# DAPLink.net
KiCad netlist of a schematic drawn in Altium Designer
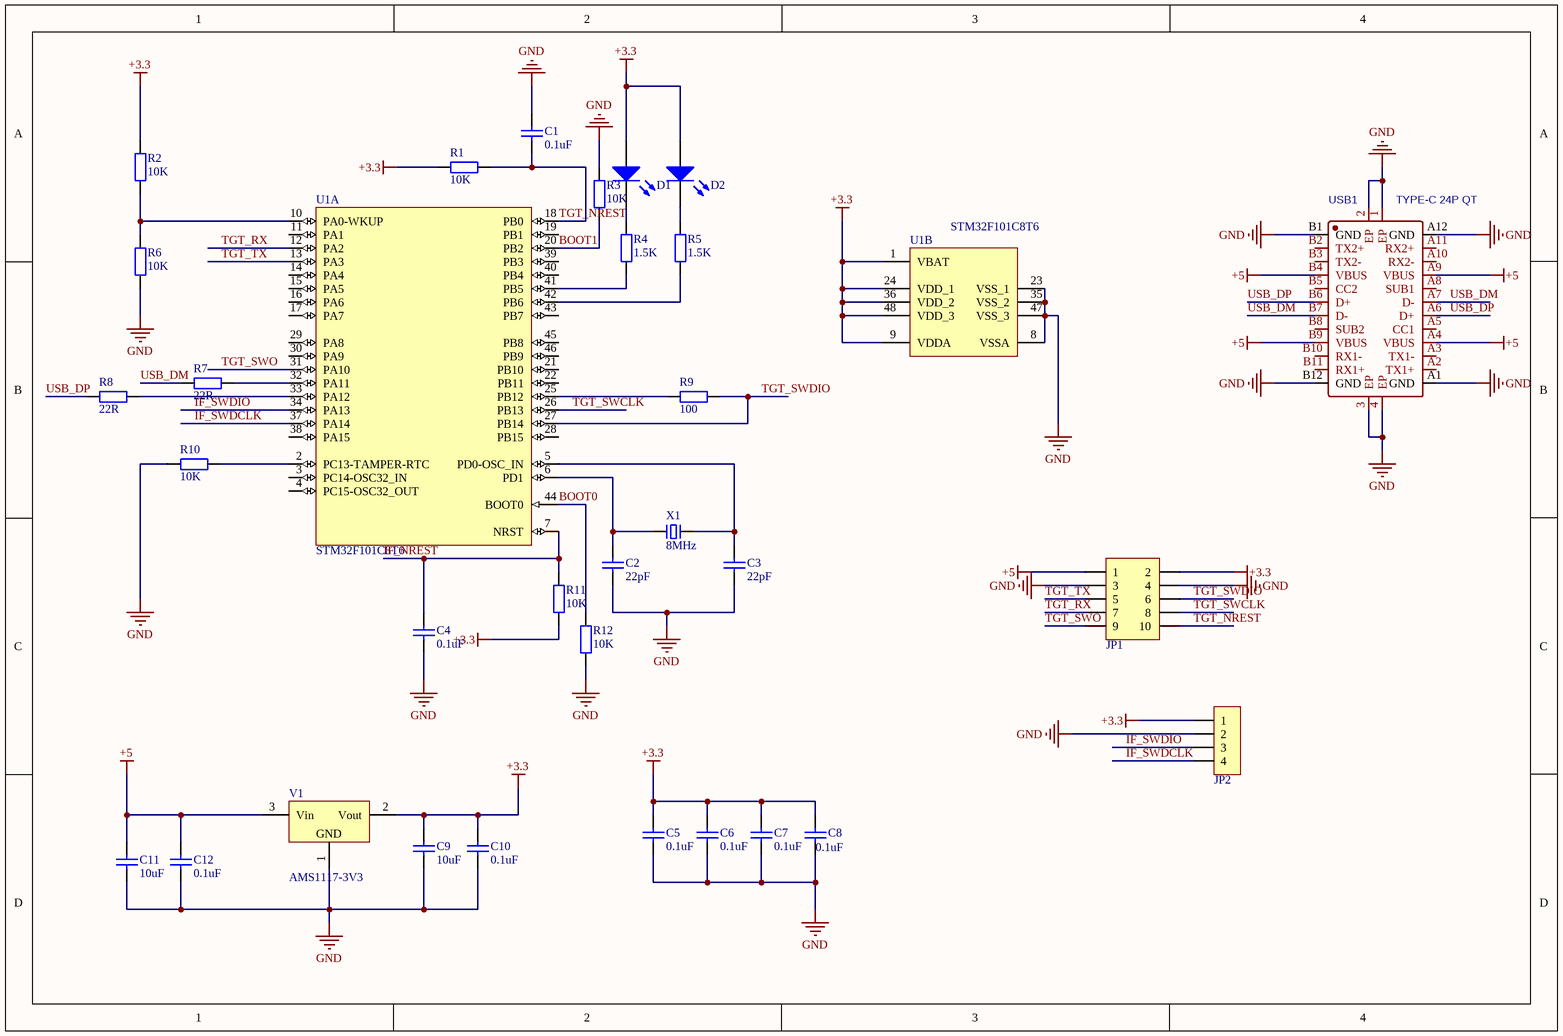
[diagram p0: DAPLink.SchDoc]

(export (version "E")
  (design (tool "Eeschema 10.0.6"))
  (components
    (comp (ref "C1")
      (value "0.1uF")
      (footprint "C0603_L")
      (description "贴片电容")
      (libsource (lib "DAPLink") (part "C"))
    )
    (comp (ref "C2")
      (value "22pF")
      (footprint "C0603_L")
      (description "贴片电容")
      (libsource (lib "DAPLink") (part "C"))
    )
    (comp (ref "C3")
      (value "22pF")
      (footprint "C0603_L")
      (description "贴片电容")
      (libsource (lib "DAPLink") (part "C"))
    )
    (comp (ref "C4")
      (value "0.1uF")
      (footprint "C0603_L")
      (description "贴片电容")
      (libsource (lib "DAPLink") (part "C"))
    )
    (comp (ref "C5")
      (value "0.1uF")
      (footprint "C0603_L")
      (description "贴片电容")
      (libsource (lib "DAPLink") (part "C"))
    )
    (comp (ref "C6")
      (value "0.1uF")
      (footprint "C0603_L")
      (description "贴片电容")
      (libsource (lib "DAPLink") (part "C"))
    )
    (comp (ref "C7")
      (value "0.1uF")
      (footprint "C0603_L")
      (description "贴片电容")
      (libsource (lib "DAPLink") (part "C"))
    )
    (comp (ref "C8")
      (value "0.1uF")
      (footprint "C0603_L")
      (description "贴片电容")
      (libsource (lib "DAPLink") (part "C"))
    )
    (comp (ref "C9")
      (value "10uF")
      (footprint "C0603_L")
      (description "贴片电容")
      (libsource (lib "DAPLink") (part "C"))
    )
    (comp (ref "C10")
      (value "0.1uF")
      (footprint "C0603_L")
      (description "贴片电容")
      (libsource (lib "DAPLink") (part "C"))
    )
    (comp (ref "C11")
      (value "10uF")
      (footprint "C0603_L")
      (description "贴片电容")
      (libsource (lib "DAPLink") (part "C"))
    )
    (comp (ref "C12")
      (value "0.1uF")
      (footprint "C0603_L")
      (description "贴片电容")
      (libsource (lib "DAPLink") (part "C"))
    )
    (comp (ref "D1")
      (value "LED")
      (footprint "LED0603_B")
      (description "发光二极管")
      (libsource (lib "DAPLink") (part "LED"))
    )
    (comp (ref "D2")
      (value "LED")
      (footprint "LED0603_G")
      (description "发光二极管")
      (libsource (lib "DAPLink") (part "LED"))
    )
    (comp (ref "JP1")
      (value "Header 5X2")
      (footprint "HDR2.54-WI-2x5P")
      (description "5*2P接插件")
      (libsource (lib "5.4 - 接插件-脚距2.54 (100mil) ") (part "Header 5X2"))
    )
    (comp (ref "JP2")
      (value "HDR-1X4")
      (footprint "HDR1.27-LI-4P")
      (description "4P接插件")
      (libsource (lib "5.1 - 接插件-脚距1.27") (part "Header 4"))
    )
    (comp (ref "R1")
      (value "10K")
      (footprint "R0603_L")
      (description "贴片电阻")
      (libsource (lib "DAPLink") (part "R"))
    )
    (comp (ref "R2")
      (value "10K")
      (footprint "R0603_L")
      (description "贴片电阻")
      (libsource (lib "DAPLink") (part "R"))
    )
    (comp (ref "R3")
      (value "10K")
      (footprint "R0603_L")
      (description "贴片电阻")
      (libsource (lib "DAPLink") (part "R"))
    )
    (comp (ref "R4")
      (value "1.5K")
      (footprint "R0603_L")
      (description "贴片电阻")
      (libsource (lib "DAPLink") (part "R"))
    )
    (comp (ref "R5")
      (value "1.5K")
      (footprint "R0603_L")
      (description "贴片电阻")
      (libsource (lib "DAPLink") (part "R"))
    )
    (comp (ref "R6")
      (value "10K")
      (footprint "R0603_L")
      (description "贴片电阻")
      (libsource (lib "DAPLink") (part "R"))
    )
    (comp (ref "R7")
      (value "22R")
      (footprint "R0603_L")
      (description "贴片电阻")
      (libsource (lib "DAPLink") (part "R"))
    )
    (comp (ref "R8")
      (value "22R")
      (footprint "R0603_L")
      (description "贴片电阻")
      (libsource (lib "DAPLink") (part "R"))
    )
    (comp (ref "R9")
      (value "100")
      (footprint "R0603_L")
      (description "贴片电阻")
      (libsource (lib "DAPLink") (part "R"))
    )
    (comp (ref "R10")
      (value "10K")
      (footprint "R0603_L")
      (description "贴片电阻")
      (libsource (lib "DAPLink") (part "R"))
    )
    (comp (ref "R11")
      (value "10K")
      (footprint "R0603_L")
      (description "贴片电阻")
      (libsource (lib "DAPLink") (part "R"))
    )
    (comp (ref "R12")
      (value "10K")
      (footprint "R0603_L")
      (description "贴片电阻")
      (libsource (lib "DAPLink") (part "R"))
    )
    (comp (ref "U1")
      (value "STM32F101C8T6")
      (footprint "LQFP48_N")
      (libsource (lib "DAPLink") (part "STM32F101C8T6"))
    )
    (comp (ref "USB1")
      (value "TYPE-C 24P QT")
      (footprint "USB-C-SMD_TYPE-C-24P-QT")
      (description "Type-C 接口")
      (fields (field (name "BOM_SUPPLIER PART") "C2681555") (field (name "CONTRIBUTOR") "LCSC"))
      (libsource (lib "nes") (part "TYPE-C 24P QT"))
    )
    (comp (ref "V1")
      (value "AMS1117-3V3")
      (footprint "SOT-223")
      (description "三端稳压芯片")
      (libsource (lib "1.1 - 电源类芯片") (part "AMS1117_SOT89"))
    )
    (comp (ref "X1")
      (value "8MHz")
      (footprint "OSC 5032-2P")
      (description "2脚无源脚晶振")
      (libsource (lib "0.5 - 保险丝-晶振-光耦") (part "XTAL-2P"))
    )
  )
  (nets
    (net (code "1") (name "+3.3") (class "Default")
      (node (ref "C10") (pin "2") (pinfunction "2_2") (pintype "passive"))
      (node (ref "C5") (pin "2") (pinfunction "2_2") (pintype "passive"))
      (node (ref "C6") (pin "2") (pinfunction "2_2") (pintype "passive"))
      (node (ref "C7") (pin "2") (pinfunction "2_2") (pintype "passive"))
      (node (ref "C8") (pin "2") (pinfunction "2_2") (pintype "passive"))
      (node (ref "C9") (pin "2") (pinfunction "2_2") (pintype "passive"))
      (node (ref "D1") (pin "1") (pinfunction "A_1") (pintype "passive"))
      (node (ref "D2") (pin "1") (pinfunction "A_1") (pintype "passive"))
      (node (ref "JP1") (pin "2") (pinfunction "2_2") (pintype "passive"))
      (node (ref "JP2") (pin "1") (pinfunction "1_1") (pintype "passive"))
      (node (ref "R1") (pin "1") (pinfunction "1_1") (pintype "passive"))
      (node (ref "R11") (pin "2") (pinfunction "2_2") (pintype "passive"))
      (node (ref "R2") (pin "1") (pinfunction "1_1") (pintype "passive"))
      (node (ref "U1") (pin "1") (pinfunction "VBAT_1") (pintype "power_in"))
      (node (ref "U1") (pin "24") (pinfunction "VDD_1_24") (pintype "power_in"))
      (node (ref "U1") (pin "36") (pinfunction "VDD_2_36") (pintype "power_in"))
      (node (ref "U1") (pin "48") (pinfunction "VDD_3_48") (pintype "power_in"))
      (node (ref "U1") (pin "9") (pinfunction "VDDA_9") (pintype "power_in"))
      (node (ref "V1") (pin "2") (pinfunction "Vout_2") (pintype "passive"))
    )
    (net (code "2") (name "+5") (class "Default")
      (node (ref "C11") (pin "2") (pinfunction "2_2") (pintype "passive"))
      (node (ref "C12") (pin "2") (pinfunction "2_2") (pintype "passive"))
      (node (ref "JP1") (pin "1") (pinfunction "1_1") (pintype "passive"))
      (node (ref "USB1") (pin "A4") (pinfunction "VBUS_A4") (pintype "passive"))
      (node (ref "USB1") (pin "A9") (pinfunction "VBUS_A9") (pintype "passive"))
      (node (ref "USB1") (pin "B4") (pinfunction "VBUS_B4") (pintype "passive"))
      (node (ref "USB1") (pin "B9") (pinfunction "VBUS_B9") (pintype "passive"))
      (node (ref "V1") (pin "3") (pinfunction "Vin_3") (pintype "passive"))
    )
    (net (code "3") (name "/BOOT0") (class "Default")
      (node (ref "R12") (pin "1") (pinfunction "1_1") (pintype "passive"))
      (node (ref "U1") (pin "44") (pinfunction "BOOT0_44") (pintype "input"))
    )
    (net (code "4") (name "/BOOT1") (class "Default")
      (node (ref "R3") (pin "2") (pinfunction "2_2") (pintype "passive"))
      (node (ref "U1") (pin "20") (pinfunction "PB2_20") (pintype "bidirectional"))
    )
    (net (code "5") (name "/IF_NREST") (class "Default")
      (node (ref "C4") (pin "2") (pinfunction "2_2") (pintype "passive"))
      (node (ref "R11") (pin "1") (pinfunction "1_1") (pintype "passive"))
      (node (ref "U1") (pin "7") (pinfunction "NRST_7") (pintype "bidirectional"))
    )
    (net (code "6") (name "/IF_SWDCLK") (class "Default")
      (node (ref "JP2") (pin "4") (pinfunction "4_4") (pintype "passive"))
      (node (ref "U1") (pin "37") (pinfunction "PA14_37") (pintype "bidirectional"))
    )
    (net (code "7") (name "/IF_SWDIO") (class "Default")
      (node (ref "JP2") (pin "3") (pinfunction "3_3") (pintype "passive"))
      (node (ref "U1") (pin "34") (pinfunction "PA13_34") (pintype "bidirectional"))
    )
    (net (code "8") (name "/TGT_NREST") (class "Default")
      (node (ref "C1") (pin "1") (pinfunction "1_1") (pintype "passive"))
      (node (ref "JP1") (pin "10") (pinfunction "10_10") (pintype "passive"))
      (node (ref "R1") (pin "2") (pinfunction "2_2") (pintype "passive"))
      (node (ref "U1") (pin "18") (pinfunction "PB0_18") (pintype "bidirectional"))
    )
    (net (code "9") (name "/TGT_RX") (class "Default")
      (node (ref "JP1") (pin "7") (pinfunction "7_7") (pintype "passive"))
      (node (ref "U1") (pin "12") (pinfunction "PA2_12") (pintype "bidirectional"))
    )
    (net (code "10") (name "/TGT_SWCLK") (class "Default")
      (node (ref "JP1") (pin "8") (pinfunction "8_8") (pintype "passive"))
      (node (ref "U1") (pin "26") (pinfunction "PB13_26") (pintype "bidirectional"))
    )
    (net (code "11") (name "/TGT_SWDIO") (class "Default")
      (node (ref "JP1") (pin "6") (pinfunction "6_6") (pintype "passive"))
      (node (ref "R9") (pin "1") (pinfunction "1_1") (pintype "passive"))
      (node (ref "U1") (pin "27") (pinfunction "PB14_27") (pintype "bidirectional"))
    )
    (net (code "12") (name "/TGT_SWO") (class "Default")
      (node (ref "JP1") (pin "9") (pinfunction "9_9") (pintype "passive"))
      (node (ref "U1") (pin "31") (pinfunction "PA10_31") (pintype "bidirectional"))
    )
    (net (code "13") (name "/TGT_TX") (class "Default")
      (node (ref "JP1") (pin "5") (pinfunction "5_5") (pintype "passive"))
      (node (ref "U1") (pin "13") (pinfunction "PA3_13") (pintype "bidirectional"))
    )
    (net (code "14") (name "/USB_DM") (class "Default")
      (node (ref "R7") (pin "2") (pinfunction "2_2") (pintype "passive"))
      (node (ref "USB1") (pin "A7") (pinfunction "D-_A7") (pintype "passive"))
      (node (ref "USB1") (pin "B7") (pinfunction "D-_B7") (pintype "passive"))
    )
    (net (code "15") (name "/USB_DP") (class "Default")
      (node (ref "R8") (pin "1") (pinfunction "1_1") (pintype "passive"))
      (node (ref "USB1") (pin "A6") (pinfunction "D+_A6") (pintype "passive"))
      (node (ref "USB1") (pin "B6") (pinfunction "D+_B6") (pintype "passive"))
    )
    (net (code "16") (name "GND") (class "Default")
      (node (ref "C1") (pin "2") (pinfunction "2_2") (pintype "passive"))
      (node (ref "C10") (pin "1") (pinfunction "1_1") (pintype "passive"))
      (node (ref "C11") (pin "1") (pinfunction "1_1") (pintype "passive"))
      (node (ref "C12") (pin "1") (pinfunction "1_1") (pintype "passive"))
      (node (ref "C2") (pin "1") (pinfunction "1_1") (pintype "passive"))
      (node (ref "C3") (pin "1") (pinfunction "1_1") (pintype "passive"))
      (node (ref "C4") (pin "1") (pinfunction "1_1") (pintype "passive"))
      (node (ref "C5") (pin "1") (pinfunction "1_1") (pintype "passive"))
      (node (ref "C6") (pin "1") (pinfunction "1_1") (pintype "passive"))
      (node (ref "C7") (pin "1") (pinfunction "1_1") (pintype "passive"))
      (node (ref "C8") (pin "1") (pinfunction "1_1") (pintype "passive"))
      (node (ref "C9") (pin "1") (pinfunction "1_1") (pintype "passive"))
      (node (ref "JP1") (pin "3") (pinfunction "3_3") (pintype "passive"))
      (node (ref "JP1") (pin "4") (pinfunction "4_4") (pintype "passive"))
      (node (ref "JP2") (pin "2") (pinfunction "2_2") (pintype "passive"))
      (node (ref "R10") (pin "2") (pinfunction "2_2") (pintype "passive"))
      (node (ref "R12") (pin "2") (pinfunction "2_2") (pintype "passive"))
      (node (ref "R3") (pin "1") (pinfunction "1_1") (pintype "passive"))
      (node (ref "R6") (pin "2") (pinfunction "2_2") (pintype "passive"))
      (node (ref "U1") (pin "23") (pinfunction "VSS_1_23") (pintype "power_in"))
      (node (ref "U1") (pin "35") (pinfunction "VSS_2_35") (pintype "power_in"))
      (node (ref "U1") (pin "47") (pinfunction "VSS_3_47") (pintype "power_in"))
      (node (ref "U1") (pin "8") (pinfunction "VSSA_8") (pintype "power_in"))
      (node (ref "USB1") (pin "1") (pinfunction "EP_1") (pintype "passive"))
      (node (ref "USB1") (pin "2") (pinfunction "EP_2") (pintype "passive"))
      (node (ref "USB1") (pin "3") (pinfunction "EP_3") (pintype "passive"))
      (node (ref "USB1") (pin "4") (pinfunction "EP_4") (pintype "passive"))
      (node (ref "USB1") (pin "A1") (pinfunction "GND_A1") (pintype "passive"))
      (node (ref "USB1") (pin "A12") (pinfunction "GND_A12") (pintype "passive"))
      (node (ref "USB1") (pin "B1") (pinfunction "GND_B1") (pintype "passive"))
      (node (ref "USB1") (pin "B12") (pinfunction "GND_B12") (pintype "passive"))
      (node (ref "V1") (pin "1") (pinfunction "GND_1") (pintype "passive"))
    )
    (net (code "17") (name "Net-(D1-K)") (class "Default")
      (node (ref "D1") (pin "2") (pinfunction "K_2") (pintype "passive"))
      (node (ref "R4") (pin "2") (pinfunction "2_2") (pintype "passive"))
    )
    (net (code "18") (name "Net-(D2-K)") (class "Default")
      (node (ref "D2") (pin "2") (pinfunction "K_2") (pintype "passive"))
      (node (ref "R5") (pin "2") (pinfunction "2_2") (pintype "passive"))
    )
    (net (code "19") (name "Net-(U1A-PA0-WKUP)") (class "Default")
      (node (ref "R2") (pin "2") (pinfunction "2_2") (pintype "passive"))
      (node (ref "R6") (pin "1") (pinfunction "1_1") (pintype "passive"))
      (node (ref "U1") (pin "10") (pinfunction "PA0-WKUP_10") (pintype "bidirectional"))
    )
    (net (code "20") (name "Net-(U1A-PA11)") (class "Default")
      (node (ref "R7") (pin "1") (pinfunction "1_1") (pintype "passive"))
      (node (ref "U1") (pin "32") (pinfunction "PA11_32") (pintype "bidirectional"))
    )
    (net (code "21") (name "Net-(U1A-PA12)") (class "Default")
      (node (ref "R8") (pin "2") (pinfunction "2_2") (pintype "passive"))
      (node (ref "U1") (pin "33") (pinfunction "PA12_33") (pintype "bidirectional"))
    )
    (net (code "22") (name "Net-(U1A-PB5)") (class "Default")
      (node (ref "R4") (pin "1") (pinfunction "1_1") (pintype "passive"))
      (node (ref "U1") (pin "41") (pinfunction "PB5_41") (pintype "bidirectional"))
    )
    (net (code "23") (name "Net-(U1A-PB6)") (class "Default")
      (node (ref "R5") (pin "1") (pinfunction "1_1") (pintype "passive"))
      (node (ref "U1") (pin "42") (pinfunction "PB6_42") (pintype "bidirectional"))
    )
    (net (code "24") (name "Net-(U1A-PB12)") (class "Default")
      (node (ref "R9") (pin "2") (pinfunction "2_2") (pintype "passive"))
      (node (ref "U1") (pin "25") (pinfunction "PB12_25") (pintype "bidirectional"))
    )
    (net (code "25") (name "Net-(U1A-PC13-TAMPER-RTC)") (class "Default")
      (node (ref "R10") (pin "1") (pinfunction "1_1") (pintype "passive"))
      (node (ref "U1") (pin "2") (pinfunction "PC13-TAMPER-RTC_2") (pintype "bidirectional"))
    )
    (net (code "26") (name "Net-(U1A-PD0-OSC_IN)") (class "Default")
      (node (ref "C3") (pin "2") (pinfunction "2_2") (pintype "passive"))
      (node (ref "U1") (pin "5") (pinfunction "PD0-OSC_IN_5") (pintype "bidirectional"))
      (node (ref "X1") (pin "1") (pinfunction "1_1") (pintype "passive"))
    )
    (net (code "27") (name "Net-(U1A-PD1)") (class "Default")
      (node (ref "C2") (pin "2") (pinfunction "2_2") (pintype "passive"))
      (node (ref "U1") (pin "6") (pinfunction "PD1_6") (pintype "bidirectional"))
      (node (ref "X1") (pin "2") (pinfunction "2_2") (pintype "passive"))
    )
    (net (code "28") (name "unconnected-(U1A-PA1-Pad11)") (class "Default")
      (node (ref "U1") (pin "11") (pinfunction "PA1_11") (pintype "bidirectional"))
    )
    (net (code "29") (name "unconnected-(U1A-PA4-Pad14)") (class "Default")
      (node (ref "U1") (pin "14") (pinfunction "PA4_14") (pintype "bidirectional"))
    )
    (net (code "30") (name "unconnected-(U1A-PA5-Pad15)") (class "Default")
      (node (ref "U1") (pin "15") (pinfunction "PA5_15") (pintype "bidirectional"))
    )
    (net (code "31") (name "unconnected-(U1A-PA6-Pad16)") (class "Default")
      (node (ref "U1") (pin "16") (pinfunction "PA6_16") (pintype "bidirectional"))
    )
    (net (code "32") (name "unconnected-(U1A-PA7-Pad17)") (class "Default")
      (node (ref "U1") (pin "17") (pinfunction "PA7_17") (pintype "bidirectional"))
    )
    (net (code "33") (name "unconnected-(U1A-PA8-Pad29)") (class "Default")
      (node (ref "U1") (pin "29") (pinfunction "PA8_29") (pintype "bidirectional"))
    )
    (net (code "34") (name "unconnected-(U1A-PA9-Pad30)") (class "Default")
      (node (ref "U1") (pin "30") (pinfunction "PA9_30") (pintype "bidirectional"))
    )
    (net (code "35") (name "unconnected-(U1A-PA15-Pad38)") (class "Default")
      (node (ref "U1") (pin "38") (pinfunction "PA15_38") (pintype "bidirectional"))
    )
    (net (code "36") (name "unconnected-(U1A-PB1-Pad19)") (class "Default")
      (node (ref "U1") (pin "19") (pinfunction "PB1_19") (pintype "bidirectional"))
    )
    (net (code "37") (name "unconnected-(U1A-PB3-Pad39)") (class "Default")
      (node (ref "U1") (pin "39") (pinfunction "PB3_39") (pintype "bidirectional"))
    )
    (net (code "38") (name "unconnected-(U1A-PB4-Pad40)") (class "Default")
      (node (ref "U1") (pin "40") (pinfunction "PB4_40") (pintype "bidirectional"))
    )
    (net (code "39") (name "unconnected-(U1A-PB7-Pad43)") (class "Default")
      (node (ref "U1") (pin "43") (pinfunction "PB7_43") (pintype "bidirectional"))
    )
    (net (code "40") (name "unconnected-(U1A-PB8-Pad45)") (class "Default")
      (node (ref "U1") (pin "45") (pinfunction "PB8_45") (pintype "bidirectional"))
    )
    (net (code "41") (name "unconnected-(U1A-PB9-Pad46)") (class "Default")
      (node (ref "U1") (pin "46") (pinfunction "PB9_46") (pintype "bidirectional"))
    )
    (net (code "42") (name "unconnected-(U1A-PB10-Pad21)") (class "Default")
      (node (ref "U1") (pin "21") (pinfunction "PB10_21") (pintype "bidirectional"))
    )
    (net (code "43") (name "unconnected-(U1A-PB11-Pad22)") (class "Default")
      (node (ref "U1") (pin "22") (pinfunction "PB11_22") (pintype "bidirectional"))
    )
    (net (code "44") (name "unconnected-(U1A-PB15-Pad28)") (class "Default")
      (node (ref "U1") (pin "28") (pinfunction "PB15_28") (pintype "bidirectional"))
    )
    (net (code "45") (name "unconnected-(U1A-PC14-OSC32_IN-Pad3)") (class "Default")
      (node (ref "U1") (pin "3") (pinfunction "PC14-OSC32_IN_3") (pintype "bidirectional"))
    )
    (net (code "46") (name "unconnected-(U1A-PC15-OSC32_OUT-Pad4)") (class "Default")
      (node (ref "U1") (pin "4") (pinfunction "PC15-OSC32_OUT_4") (pintype "bidirectional"))
    )
    (net (code "47") (name "unconnected-(USB1-CC1-PadA5)") (class "Default")
      (node (ref "USB1") (pin "A5") (pinfunction "CC1_A5") (pintype "passive"))
    )
    (net (code "48") (name "unconnected-(USB1-CC2-PadB5)") (class "Default")
      (node (ref "USB1") (pin "B5") (pinfunction "CC2_B5") (pintype "passive"))
    )
    (net (code "49") (name "unconnected-(USB1-RX1+-PadB11)") (class "Default")
      (node (ref "USB1") (pin "B11") (pinfunction "RX1+_B11") (pintype "passive"))
    )
    (net (code "50") (name "unconnected-(USB1-RX1--PadB10)") (class "Default")
      (node (ref "USB1") (pin "B10") (pinfunction "RX1-_B10") (pintype "passive"))
    )
    (net (code "51") (name "unconnected-(USB1-RX2+-PadA11)") (class "Default")
      (node (ref "USB1") (pin "A11") (pinfunction "RX2+_A11") (pintype "passive"))
    )
    (net (code "52") (name "unconnected-(USB1-RX2--PadA10)") (class "Default")
      (node (ref "USB1") (pin "A10") (pinfunction "RX2-_A10") (pintype "passive"))
    )
    (net (code "53") (name "unconnected-(USB1-SUB1-PadA8)") (class "Default")
      (node (ref "USB1") (pin "A8") (pinfunction "SUB1_A8") (pintype "passive"))
    )
    (net (code "54") (name "unconnected-(USB1-SUB2-PadB8)") (class "Default")
      (node (ref "USB1") (pin "B8") (pinfunction "SUB2_B8") (pintype "passive"))
    )
    (net (code "55") (name "unconnected-(USB1-TX1+-PadA2)") (class "Default")
      (node (ref "USB1") (pin "A2") (pinfunction "TX1+_A2") (pintype "passive"))
    )
    (net (code "56") (name "unconnected-(USB1-TX1--PadA3)") (class "Default")
      (node (ref "USB1") (pin "A3") (pinfunction "TX1-_A3") (pintype "passive"))
    )
    (net (code "57") (name "unconnected-(USB1-TX2+-PadB2)") (class "Default")
      (node (ref "USB1") (pin "B2") (pinfunction "TX2+_B2") (pintype "passive"))
    )
    (net (code "58") (name "unconnected-(USB1-TX2--PadB3)") (class "Default")
      (node (ref "USB1") (pin "B3") (pinfunction "TX2-_B3") (pintype "passive"))
    )
  )
)
